# MotionSense.net
KiCad netlist of a schematic drawn in EAGLE
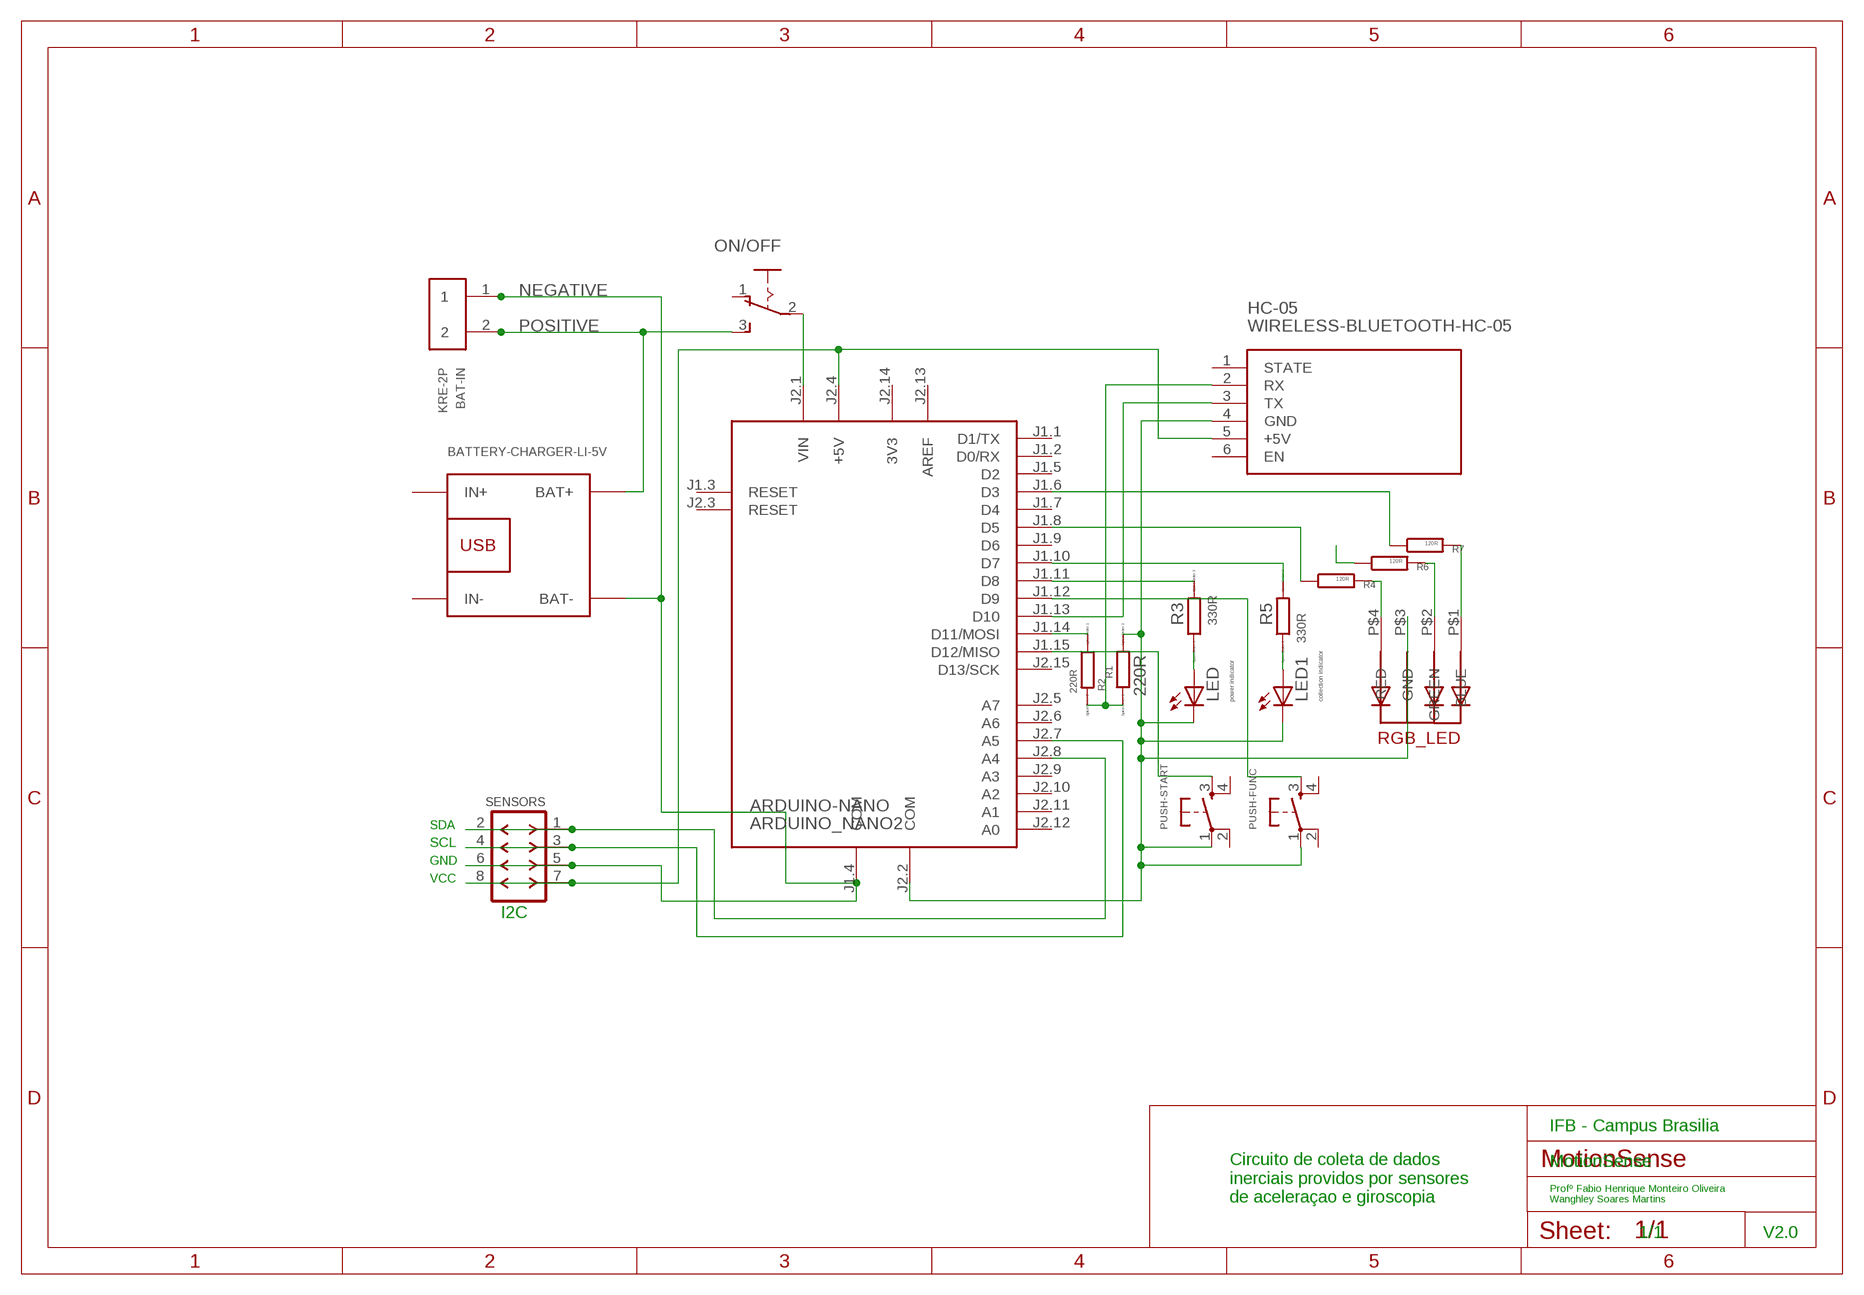
[diagram p0: schematic, sheet 1]

(export (version "E")
  (design (tool "Eeschema 10.0.6"))
  (components
    (comp (ref "ARDUINO-NANO")
      (value "ARDUINO_NANO2")
      (footprint "eagle-import:ARDUINO_NANO2")
      (libsource (lib "eagle-import") (part "ARDUINO_NANO2"))
    )
    (comp (ref "BAT-IN")
      (value "KRE-2P")
      (footprint "eagle-import:KRE-2P")
      (libsource (lib "eagle-import") (part "KRE-2P"))
    )
    (comp (ref "HC-05")
      (value "WIRELESS-BLUETOOTH-HC-05")
      (footprint "eagle-import:WIRELESS-BLUETOOTH-HC-05")
      (libsource (lib "eagle-import") (part "WIRELESS-BLUETOOTH-HC-05"))
    )
    (comp (ref "LED")
      (value "power indicator")
      (footprint "eagle-import:LED5MM")
      (libsource (lib "eagle-import") (part "LED5MM"))
    )
    (comp (ref "LED1")
      (value "collection indicator")
      (footprint "eagle-import:LED5MM")
      (libsource (lib "eagle-import") (part "LED5MM"))
    )
    (comp (ref "ON/OFF")
      (value "255SB")
      (footprint "eagle-import:255SB")
      (libsource (lib "eagle-import") (part "255SB"))
    )
    (comp (ref "PUSH-FUNC")
      (value "DTS-6")
      (footprint "eagle-import:DTS-6")
      (libsource (lib "eagle-import") (part "DTS-6"))
    )
    (comp (ref "PUSH-START")
      (value "DTS-6")
      (footprint "eagle-import:DTS-6")
      (libsource (lib "eagle-import") (part "DTS-6"))
    )
    (comp (ref "R1")
      (value "220R")
      (footprint "eagle-import:0207_10")
      (libsource (lib "eagle-import") (part "R0207/10"))
    )
    (comp (ref "R2")
      (value "220R")
      (footprint "eagle-import:0207_10")
      (libsource (lib "eagle-import") (part "R0207/10"))
    )
    (comp (ref "R3")
      (value "330R")
      (footprint "eagle-import:0207_10")
      (libsource (lib "eagle-import") (part "R0207/10"))
    )
    (comp (ref "R4")
      (value "120R")
      (footprint "eagle-import:0204_7")
      (libsource (lib "eagle-import") (part "R-EU_0204/7"))
    )
    (comp (ref "R5")
      (value "330R")
      (footprint "eagle-import:0207_10")
      (libsource (lib "eagle-import") (part "R0207/10"))
    )
    (comp (ref "R6")
      (value "120R")
      (footprint "eagle-import:0204_7")
      (libsource (lib "eagle-import") (part "R-EU_0204/7"))
    )
    (comp (ref "R7")
      (value "120R")
      (footprint "eagle-import:0204_7")
      (libsource (lib "eagle-import") (part "R-EU_0204/7"))
    )
    (comp (ref "RGB_LED")
      (value "5MMRGBLED")
      (footprint "eagle-import:LED5MMRGB")
      (libsource (lib "eagle-import") (part "5MMRGBLED"))
    )
    (comp (ref "SENSORS")
      (value "F-2X04-DIL-2MM_M")
      (footprint "eagle-import:DIL-2MM-2X04_M")
      (libsource (lib "eagle-import") (part "F-2X04-DIL-2MM_M"))
    )
    (comp (ref "U$1")
      (value "BATTERY-CHARGER-LI-5V")
      (footprint "eagle-import:BATTERY-CHARGER-LI-5V")
      (libsource (lib "eagle-import") (part "BATTERY-CHARGER-LI-5V"))
    )
  )
  (nets
    (net (code "1") (name "/3V3") (class "Default")
      (node (ref "ARDUINO-NANO") (pin "J2.14") (pinfunction "3V3_J2.14") (pintype "power_in"))
    )
    (net (code "2") (name "/AREF") (class "Default")
      (node (ref "ARDUINO-NANO") (pin "J2.13") (pinfunction "AREF_J2.13") (pintype "power_in"))
    )
    (net (code "3") (name "/NEGATIVE") (class "Default")
      (node (ref "ARDUINO-NANO") (pin "J1.4") (pinfunction "COM_J1.4") (pintype "power_in"))
      (node (ref "BAT-IN") (pin "1") (pinfunction "1_1") (pintype "bidirectional"))
      (node (ref "SENSORS") (pin "5") (pinfunction "5_5") (pintype "passive"))
      (node (ref "SENSORS") (pin "6") (pinfunction "6_6") (pintype "passive"))
      (node (ref "U$1") (pin "BAT-") (pinfunction "BAT-_BAT-") (pintype "bidirectional"))
    )
    (net (code "4") (name "/POSITIVE") (class "Default")
      (node (ref "BAT-IN") (pin "2") (pinfunction "2_2") (pintype "bidirectional"))
      (node (ref "ON/OFF") (pin "3") (pinfunction "S_3") (pintype "passive"))
      (node (ref "U$1") (pin "BAT+") (pinfunction "BAT+_BAT+") (pintype "bidirectional"))
    )
    (net (code "5") (name "Net-(ARDUINO-NANO-+5V)") (class "Default")
      (node (ref "ARDUINO-NANO") (pin "J2.4") (pinfunction "+5V_J2.4") (pintype "power_in"))
      (node (ref "HC-05") (pin "5") (pinfunction "+5V_5") (pintype "power_in"))
      (node (ref "SENSORS") (pin "7") (pinfunction "7_7") (pintype "passive"))
      (node (ref "SENSORS") (pin "8") (pinfunction "8_8") (pintype "passive"))
    )
    (net (code "6") (name "Net-(ARDUINO-NANO-A4)") (class "Default")
      (node (ref "ARDUINO-NANO") (pin "J2.8") (pinfunction "A4_J2.8") (pintype "bidirectional"))
      (node (ref "SENSORS") (pin "1") (pinfunction "1_1") (pintype "passive"))
      (node (ref "SENSORS") (pin "2") (pinfunction "2_2") (pintype "passive"))
    )
    (net (code "7") (name "Net-(ARDUINO-NANO-A5)") (class "Default")
      (node (ref "ARDUINO-NANO") (pin "J2.7") (pinfunction "A5_J2.7") (pintype "bidirectional"))
      (node (ref "SENSORS") (pin "3") (pinfunction "3_3") (pintype "passive"))
      (node (ref "SENSORS") (pin "4") (pinfunction "4_4") (pintype "passive"))
    )
    (net (code "8") (name "Net-(ARDUINO-NANO-D3)") (class "Default")
      (node (ref "ARDUINO-NANO") (pin "J1.6") (pinfunction "D3_J1.6") (pintype "bidirectional"))
      (node (ref "R7") (pin "1") (pinfunction "1_1") (pintype "passive"))
    )
    (net (code "9") (name "Net-(ARDUINO-NANO-D5)") (class "Default")
      (node (ref "ARDUINO-NANO") (pin "J1.8") (pinfunction "D5_J1.8") (pintype "bidirectional"))
      (node (ref "R4") (pin "1") (pinfunction "1_1") (pintype "passive"))
    )
    (net (code "10") (name "Net-(ARDUINO-NANO-D7)") (class "Default")
      (node (ref "ARDUINO-NANO") (pin "J1.10") (pinfunction "D7_J1.10") (pintype "bidirectional"))
      (node (ref "R5") (pin "2") (pinfunction "2_2") (pintype "passive"))
    )
    (net (code "11") (name "Net-(ARDUINO-NANO-D8)") (class "Default")
      (node (ref "ARDUINO-NANO") (pin "J1.11") (pinfunction "D8_J1.11") (pintype "bidirectional"))
      (node (ref "R3") (pin "2") (pinfunction "2_2") (pintype "passive"))
    )
    (net (code "12") (name "Net-(ARDUINO-NANO-D9)") (class "Default")
      (node (ref "ARDUINO-NANO") (pin "J1.12") (pinfunction "D9_J1.12") (pintype "bidirectional"))
      (node (ref "PUSH-FUNC") (pin "3") (pinfunction "3_3") (pintype "passive"))
    )
    (net (code "13") (name "Net-(ARDUINO-NANO-D10)") (class "Default")
      (node (ref "ARDUINO-NANO") (pin "J1.13") (pinfunction "D10_J1.13") (pintype "bidirectional"))
      (node (ref "HC-05") (pin "3") (pinfunction "TX_3") (pintype "bidirectional"))
    )
    (net (code "14") (name "Net-(ARDUINO-NANO-D11{slash}MOSI)") (class "Default")
      (node (ref "ARDUINO-NANO") (pin "J1.14") (pinfunction "D11/MOSI_J1.14") (pintype "bidirectional"))
      (node (ref "R2") (pin "1") (pinfunction "1_1") (pintype "passive"))
    )
    (net (code "15") (name "Net-(ARDUINO-NANO-D12{slash}MISO)") (class "Default")
      (node (ref "ARDUINO-NANO") (pin "J1.15") (pinfunction "D12/MISO_J1.15") (pintype "bidirectional"))
      (node (ref "PUSH-START") (pin "3") (pinfunction "3_3") (pintype "passive"))
    )
    (net (code "16") (name "Net-(ARDUINO-NANO-VIN)") (class "Default")
      (node (ref "ARDUINO-NANO") (pin "J2.1") (pinfunction "VIN_J2.1") (pintype "power_in"))
      (node (ref "ON/OFF") (pin "2") (pinfunction "P_2") (pintype "passive"))
    )
    (net (code "17") (name "Net-(HC-05-GND)") (class "Default")
      (node (ref "ARDUINO-NANO") (pin "J2.2") (pinfunction "COM_J2.2") (pintype "power_in"))
      (node (ref "HC-05") (pin "4") (pinfunction "GND_4") (pintype "power_in"))
      (node (ref "LED") (pin "K") (pinfunction "C_K") (pintype "passive"))
      (node (ref "LED1") (pin "K") (pinfunction "C_K") (pintype "passive"))
      (node (ref "PUSH-FUNC") (pin "1") (pinfunction "1_1") (pintype "passive"))
      (node (ref "PUSH-START") (pin "1") (pinfunction "1_1") (pintype "passive"))
      (node (ref "R1") (pin "2") (pinfunction "2_2") (pintype "passive"))
      (node (ref "RGB_LED") (pin "P$3") (pinfunction "GND_P$3") (pintype "bidirectional"))
    )
    (net (code "18") (name "Net-(HC-05-RX)") (class "Default")
      (node (ref "HC-05") (pin "2") (pinfunction "RX_2") (pintype "bidirectional"))
      (node (ref "R1") (pin "1") (pinfunction "1_1") (pintype "passive"))
      (node (ref "R2") (pin "2") (pinfunction "2_2") (pintype "passive"))
    )
    (net (code "19") (name "Net-(LED-PadA)") (class "Default")
      (node (ref "LED") (pin "A") (pinfunction "A_A") (pintype "passive"))
      (node (ref "R3") (pin "1") (pinfunction "1_1") (pintype "passive"))
    )
    (net (code "20") (name "Net-(LED1-PadA)") (class "Default")
      (node (ref "LED1") (pin "A") (pinfunction "A_A") (pintype "passive"))
      (node (ref "R5") (pin "1") (pinfunction "1_1") (pintype "passive"))
    )
    (net (code "21") (name "Net-(RGB_LED-BLUE)") (class "Default")
      (node (ref "R7") (pin "2") (pinfunction "2_2") (pintype "passive"))
      (node (ref "RGB_LED") (pin "P$1") (pinfunction "BLUE_P$1") (pintype "bidirectional"))
    )
    (net (code "22") (name "Net-(RGB_LED-GREEN)") (class "Default")
      (node (ref "R6") (pin "2") (pinfunction "2_2") (pintype "passive"))
      (node (ref "RGB_LED") (pin "P$2") (pinfunction "GREEN_P$2") (pintype "bidirectional"))
    )
    (net (code "23") (name "Net-(RGB_LED-RED)") (class "Default")
      (node (ref "R4") (pin "2") (pinfunction "2_2") (pintype "passive"))
      (node (ref "RGB_LED") (pin "P$4") (pinfunction "RED_P$4") (pintype "bidirectional"))
    )
    (net (code "24") (name "unconnected-(ARDUINO-NANO-A0-PadJ2.12)") (class "Default")
      (node (ref "ARDUINO-NANO") (pin "J2.12") (pinfunction "A0_J2.12") (pintype "bidirectional"))
    )
    (net (code "25") (name "unconnected-(ARDUINO-NANO-A1-PadJ2.11)") (class "Default")
      (node (ref "ARDUINO-NANO") (pin "J2.11") (pinfunction "A1_J2.11") (pintype "bidirectional"))
    )
    (net (code "26") (name "unconnected-(ARDUINO-NANO-A2-PadJ2.10)") (class "Default")
      (node (ref "ARDUINO-NANO") (pin "J2.10") (pinfunction "A2_J2.10") (pintype "bidirectional"))
    )
    (net (code "27") (name "unconnected-(ARDUINO-NANO-A3-PadJ2.9)") (class "Default")
      (node (ref "ARDUINO-NANO") (pin "J2.9") (pinfunction "A3_J2.9") (pintype "bidirectional"))
    )
    (net (code "28") (name "unconnected-(ARDUINO-NANO-A6-PadJ2.6)") (class "Default")
      (node (ref "ARDUINO-NANO") (pin "J2.6") (pinfunction "A6_J2.6") (pintype "bidirectional"))
    )
    (net (code "29") (name "unconnected-(ARDUINO-NANO-A7-PadJ2.5)") (class "Default")
      (node (ref "ARDUINO-NANO") (pin "J2.5") (pinfunction "A7_J2.5") (pintype "bidirectional"))
    )
    (net (code "30") (name "unconnected-(ARDUINO-NANO-D0{slash}RX-PadJ1.2)") (class "Default")
      (node (ref "ARDUINO-NANO") (pin "J1.2") (pinfunction "D0/RX_J1.2") (pintype "bidirectional"))
    )
    (net (code "31") (name "unconnected-(ARDUINO-NANO-D1{slash}TX-PadJ1.1)") (class "Default")
      (node (ref "ARDUINO-NANO") (pin "J1.1") (pinfunction "D1/TX_J1.1") (pintype "bidirectional"))
    )
    (net (code "32") (name "unconnected-(ARDUINO-NANO-D2-PadJ1.5)") (class "Default")
      (node (ref "ARDUINO-NANO") (pin "J1.5") (pinfunction "D2_J1.5") (pintype "bidirectional"))
    )
    (net (code "33") (name "unconnected-(ARDUINO-NANO-D4-PadJ1.7)") (class "Default")
      (node (ref "ARDUINO-NANO") (pin "J1.7") (pinfunction "D4_J1.7") (pintype "bidirectional"))
    )
    (net (code "34") (name "unconnected-(ARDUINO-NANO-D6-PadJ1.9)") (class "Default")
      (node (ref "ARDUINO-NANO") (pin "J1.9") (pinfunction "D6_J1.9") (pintype "bidirectional"))
    )
    (net (code "35") (name "unconnected-(ARDUINO-NANO-D13{slash}SCK-PadJ2.15)") (class "Default")
      (node (ref "ARDUINO-NANO") (pin "J2.15") (pinfunction "D13/SCK_J2.15") (pintype "bidirectional"))
    )
    (net (code "36") (name "unconnected-(ARDUINO-NANO-RESET-PadJ1.3)") (class "Default")
      (node (ref "ARDUINO-NANO") (pin "J1.3") (pinfunction "RESET_J1.3") (pintype "bidirectional"))
    )
    (net (code "37") (name "unconnected-(ARDUINO-NANO-RESET-PadJ2.3)") (class "Default")
      (node (ref "ARDUINO-NANO") (pin "J2.3") (pinfunction "RESET_J2.3") (pintype "bidirectional"))
    )
    (net (code "38") (name "unconnected-(HC-05-EN-Pad6)") (class "Default")
      (node (ref "HC-05") (pin "6") (pinfunction "EN_6") (pintype "bidirectional"))
    )
    (net (code "39") (name "unconnected-(HC-05-STATE-Pad1)") (class "Default")
      (node (ref "HC-05") (pin "1") (pinfunction "STATE_1") (pintype "bidirectional"))
    )
    (net (code "40") (name "unconnected-(ON/OFF-O-Pad1)") (class "Default")
      (node (ref "ON/OFF") (pin "1") (pinfunction "O_1") (pintype "passive"))
    )
    (net (code "41") (name "unconnected-(PUSH-FUNC-Pad2)") (class "Default")
      (node (ref "PUSH-FUNC") (pin "2") (pinfunction "2_2") (pintype "passive"))
    )
    (net (code "42") (name "unconnected-(PUSH-FUNC-Pad4)") (class "Default")
      (node (ref "PUSH-FUNC") (pin "4") (pinfunction "4_4") (pintype "passive"))
    )
    (net (code "43") (name "unconnected-(PUSH-START-Pad2)") (class "Default")
      (node (ref "PUSH-START") (pin "2") (pinfunction "2_2") (pintype "passive"))
    )
    (net (code "44") (name "unconnected-(PUSH-START-Pad4)") (class "Default")
      (node (ref "PUSH-START") (pin "4") (pinfunction "4_4") (pintype "passive"))
    )
    (net (code "45") (name "unconnected-(R6-Pad1)") (class "Default")
      (node (ref "R6") (pin "1") (pinfunction "1_1") (pintype "passive"))
    )
    (net (code "46") (name "unconnected-(U$1-PadIN+)") (class "Default")
      (node (ref "U$1") (pin "IN+") (pinfunction "IN+_IN+") (pintype "bidirectional"))
    )
    (net (code "47") (name "unconnected-(U$1-PadIN-)") (class "Default")
      (node (ref "U$1") (pin "IN-") (pinfunction "IN-_IN-") (pintype "bidirectional"))
    )
  )
)
